# Main_Board.net
KiCad netlist of a schematic drawn in Altium Designer
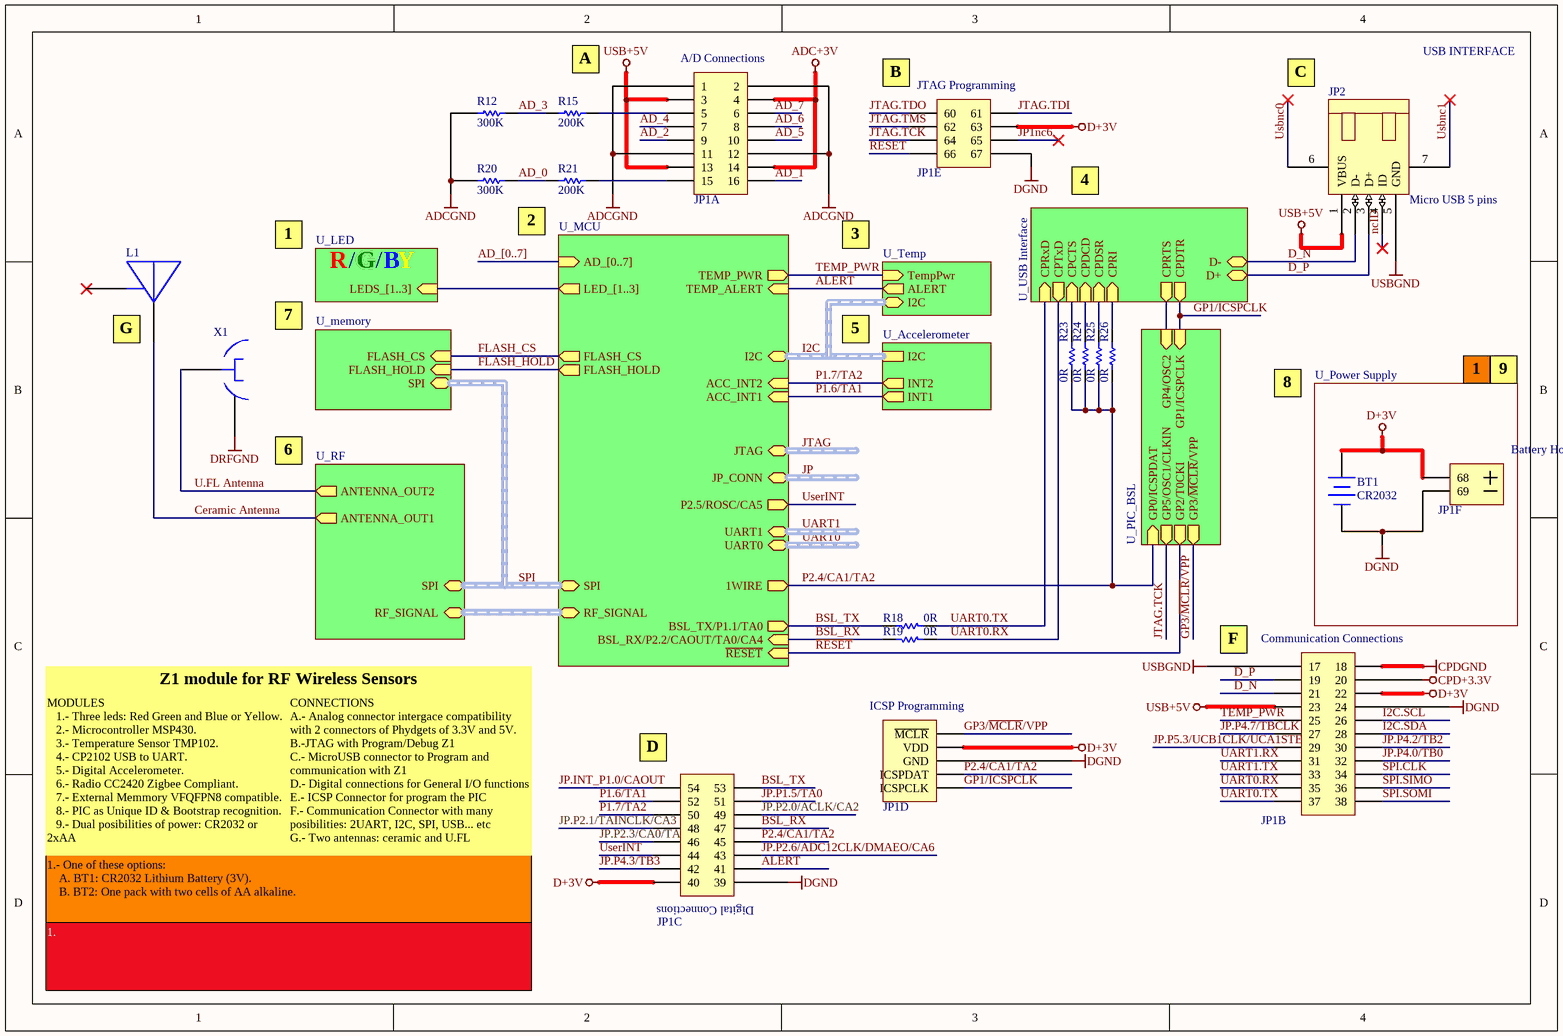
[diagram p0: Main Board.SchDoc]

(export (version "E")
  (design (tool "Eeschema 10.0.6"))
  (components
    (comp (ref "BT1")
      (value "CR2032")
      (footprint "CR2032 - 796136-1")
      (description "Multicell Battery")
      (libsource (lib "Z1_Project") (part "Battery"))
    )
    (comp (ref "JP1")
      (value "Z1 Expansion Connector")
      (footprint "Z1 Expansion Connectors_RC2")
      (libsource (lib "Z1_Project") (part "Z1_RC1"))
    )
    (comp (ref "JP2")
      (value "Micro USB 5 pins")
      (footprint "ZX62D-B-5P8")
      (libsource (lib "Z1_Project") (part "USB 5 pins"))
    )
    (comp (ref "L1")
      (value "Ceramic Antenna")
      (footprint "YAGEO - CAW431115300245")
      (description "ANT 2.4GHZ 802.11 BLUETOOTH SMD")
      (libsource (lib "Z1_Project") (part "5.3x2.2 TDMA Antenna_1"))
    )
    (comp (ref "R12")
      (value "300K")
      (footprint "CR1005-0402")
      (description "Semiconductor Resistor")
      (fields (field (name "MANUFACTURER") "Generic Components") (field (name "Comment") "Res Semi"))
      (libsource (lib "Z1_Project") (part "Res Semi"))
    )
    (comp (ref "R15")
      (value "200K")
      (footprint "CR1005-0402")
      (description "Semiconductor Resistor")
      (fields (field (name "MANUFACTURER") "Generic Components") (field (name "Comment") "Res Semi"))
      (libsource (lib "Z1_Project") (part "Res Semi"))
    )
    (comp (ref "R18")
      (value "0R")
      (footprint "CR-0402-AL")
      (description "RES ZERO OHM 1/10W 5% 0402 SMD")
      (fields (field (name "Comment") "Res Semi"))
      (libsource (lib "Z1_Project") (part "Res Semi"))
    )
    (comp (ref "R19")
      (value "0R")
      (footprint "CR-0402-AL")
      (description "RES ZERO OHM 1/10W 5% 0402 SMD")
      (fields (field (name "Comment") "Res Semi"))
      (libsource (lib "Z1_Project") (part "Res Semi"))
    )
    (comp (ref "R20")
      (value "300K")
      (footprint "CR1005-0402")
      (description "Semiconductor Resistor")
      (fields (field (name "MANUFACTURER") "Generic Components") (field (name "Comment") "Res Semi"))
      (libsource (lib "Z1_Project") (part "Res Semi"))
    )
    (comp (ref "R21")
      (value "200K")
      (footprint "CR1005-0402")
      (description "Semiconductor Resistor")
      (fields (field (name "MANUFACTURER") "Generic Components") (field (name "Comment") "Res Semi"))
      (libsource (lib "Z1_Project") (part "Res Semi"))
    )
    (comp (ref "R23")
      (value "0R")
      (footprint "CR-0402-AL")
      (description "Semiconductor Resistor")
      (fields (field (name "MANUFACTURER") "Generic Components") (field (name "Comment") "Res Semi"))
      (libsource (lib "Z1_Project") (part "Res Semi"))
    )
    (comp (ref "R24")
      (value "0R")
      (footprint "CR-0402-AL")
      (description "Semiconductor Resistor")
      (fields (field (name "MANUFACTURER") "Generic Components") (field (name "Comment") "Res Semi"))
      (libsource (lib "Z1_Project") (part "Res Semi"))
    )
    (comp (ref "R25")
      (value "0R")
      (footprint "CR-0402-AL")
      (description "Semiconductor Resistor")
      (fields (field (name "MANUFACTURER") "Generic Components") (field (name "Comment") "Res Semi"))
      (libsource (lib "Z1_Project") (part "Res Semi"))
    )
    (comp (ref "R26")
      (value "0R")
      (footprint "CR-0402-AL")
      (description "Semiconductor Resistor")
      (fields (field (name "MANUFACTURER") "Generic Components") (field (name "Comment") "Res Semi"))
      (libsource (lib "Z1_Project") (part "Res Semi"))
    )
    (comp (ref "X1")
      (value "U.FL RF Connector")
      (footprint "U.FL")
      (description "CONN RF MICROCOAXIAL SMD GOLD")
      (libsource (lib "Z1_Project") (part "AntennaOmnidirectional"))
    )
  )
  (nets
    (net (code "7") (name "/AD_0") (class "Default")
      (node (ref "R20") (pin "1") (pinfunction "1_1") (pintype "passive"))
      (node (ref "R21") (pin "2") (pinfunction "2_2") (pintype "passive"))
    )
    (net (code "8") (name "/AD_1") (class "Default")
      (node (ref "JP1") (pin "16") (pinfunction "16_16") (pintype "passive"))
    )
    (net (code "9") (name "/AD_2") (class "Default")
      (node (ref "JP1") (pin "9") (pinfunction "9_9") (pintype "passive"))
    )
    (net (code "10") (name "/AD_3") (class "Default")
      (node (ref "R12") (pin "1") (pinfunction "1_1") (pintype "passive"))
      (node (ref "R15") (pin "2") (pinfunction "2_2") (pintype "passive"))
    )
    (net (code "11") (name "/AD_4") (class "Default")
      (node (ref "JP1") (pin "7") (pinfunction "7_7") (pintype "passive"))
    )
    (net (code "12") (name "/AD_5") (class "Default")
      (node (ref "JP1") (pin "10") (pinfunction "10_10") (pintype "passive"))
    )
    (net (code "13") (name "/AD_6") (class "Default")
      (node (ref "JP1") (pin "8") (pinfunction "8_8") (pintype "passive"))
    )
    (net (code "14") (name "/AD_7") (class "Default")
      (node (ref "JP1") (pin "6") (pinfunction "6_6") (pintype "passive"))
    )
    (net (code "16") (name "/ALERT") (class "Default")
      (node (ref "JP1") (pin "41") (pinfunction "41_41") (pintype "passive"))
    )
    (net (code "17") (name "/BSL_RX") (class "Default")
      (node (ref "JP1") (pin "47") (pinfunction "47_47") (pintype "passive"))
      (node (ref "R19") (pin "2") (pinfunction "2_2") (pintype "passive"))
    )
    (net (code "18") (name "/BSL_TX") (class "Default")
      (node (ref "JP1") (pin "53") (pinfunction "53_53") (pintype "passive"))
      (node (ref "R18") (pin "2") (pinfunction "2_2") (pintype "passive"))
    )
    (net (code "19") (name "/CPCTS") (class "Default")
      (node (ref "R23") (pin "1") (pinfunction "1_1") (pintype "passive"))
    )
    (net (code "20") (name "/CPDCD") (class "Default")
      (node (ref "R24") (pin "1") (pinfunction "1_1") (pintype "passive"))
    )
    (net (code "21") (name "/CPDSR") (class "Default")
      (node (ref "R25") (pin "1") (pinfunction "1_1") (pintype "passive"))
    )
    (net (code "22") (name "/CPRI") (class "Default")
      (node (ref "R26") (pin "1") (pinfunction "1_1") (pintype "passive"))
    )
    (net (code "24") (name "/Ceramic Antenna") (class "Default")
      (node (ref "L1") (pin "1") (pinfunction "+_1") (pintype "passive"))
    )
    (net (code "25") (name "/D_N") (class "Default")
      (node (ref "JP1") (pin "21") (pinfunction "21_21") (pintype "passive"))
      (node (ref "JP2") (pin "2") (pinfunction "D-_2") (pintype "bidirectional"))
    )
    (net (code "26") (name "/D_P") (class "Default")
      (node (ref "JP1") (pin "19") (pinfunction "19_19") (pintype "passive"))
      (node (ref "JP2") (pin "3") (pinfunction "D+_3") (pintype "bidirectional"))
    )
    (net (code "29") (name "/GP1{slash}ICSPCLK") (class "Default")
      (node (ref "JP1") (pin "59") (pinfunction "59_59") (pintype "passive"))
    )
    (net (code "30") (name "/GP3{slash}~{MCLR}{slash}VPP") (class "Default")
      (node (ref "JP1") (pin "55") (pinfunction "55_55") (pintype "passive"))
    )
    (net (code "31") (name "/I2C.SCL") (class "Default")
      (node (ref "JP1") (pin "26") (pinfunction "26_26") (pintype "passive"))
    )
    (net (code "32") (name "/I2C.SDA") (class "Default")
      (node (ref "JP1") (pin "28") (pinfunction "28_28") (pintype "passive"))
    )
    (net (code "34") (name "/JP.INT_P1.0{slash}CAOUT") (class "Default")
      (node (ref "JP1") (pin "54") (pinfunction "54_54") (pintype "passive"))
    )
    (net (code "35") (name "/JP.P1.5{slash}TA0") (class "Default")
      (node (ref "JP1") (pin "51") (pinfunction "51_51") (pintype "passive"))
    )
    (net (code "36") (name "/JP.P2.0{slash}ACLK{slash}CA2") (class "Default")
      (node (ref "JP1") (pin "49") (pinfunction "49_49") (pintype "passive"))
    )
    (net (code "37") (name "/JP.P2.1{slash}TAINCLK{slash}CA3") (class "Default")
      (node (ref "JP1") (pin "48") (pinfunction "48_48") (pintype "passive"))
    )
    (net (code "38") (name "/JP.P2.3{slash}CA0{slash}TA1") (class "Default")
      (node (ref "JP1") (pin "46") (pinfunction "46_46") (pintype "passive"))
    )
    (net (code "39") (name "/JP.P2.6{slash}ADC12CLK{slash}DMAEO{slash}CA6") (class "Default")
      (node (ref "JP1") (pin "43") (pinfunction "43_43") (pintype "passive"))
    )
    (net (code "40") (name "/JP.P4.0{slash}TB0") (class "Default")
      (node (ref "JP1") (pin "32") (pinfunction "32_32") (pintype "passive"))
    )
    (net (code "41") (name "/JP.P4.2{slash}TB2") (class "Default")
      (node (ref "JP1") (pin "30") (pinfunction "30_30") (pintype "passive"))
    )
    (net (code "42") (name "/JP.P4.3{slash}TB3") (class "Default")
      (node (ref "JP1") (pin "42") (pinfunction "42_42") (pintype "passive"))
    )
    (net (code "43") (name "/JP.P4.7{slash}TBCLK") (class "Default")
      (node (ref "JP1") (pin "27") (pinfunction "27_27") (pintype "passive"))
    )
    (net (code "44") (name "/JP.P5.3{slash}UCB1CLK{slash}UCA1STE") (class "Default")
      (node (ref "JP1") (pin "29") (pinfunction "29_29") (pintype "passive"))
    )
    (net (code "45") (name "/JP1nc6") (class "Default")
      (node (ref "JP1") (pin "65") (pinfunction "65_65") (pintype "passive+no_connect"))
    )
    (net (code "46") (name "/JTAG.TCK") (class "Default")
      (node (ref "JP1") (pin "64") (pinfunction "64_64") (pintype "passive"))
    )
    (net (code "47") (name "/JTAG.TDI") (class "Default")
      (node (ref "JP1") (pin "61") (pinfunction "61_61") (pintype "passive"))
    )
    (net (code "48") (name "/JTAG.TDO") (class "Default")
      (node (ref "JP1") (pin "60") (pinfunction "60_60") (pintype "passive"))
    )
    (net (code "49") (name "/JTAG.TMS") (class "Default")
      (node (ref "JP1") (pin "62") (pinfunction "62_62") (pintype "passive"))
    )
    (net (code "51") (name "/P1.6{slash}TA1") (class "Default")
      (node (ref "JP1") (pin "52") (pinfunction "52_52") (pintype "passive"))
    )
    (net (code "52") (name "/P1.7{slash}TA2") (class "Default")
      (node (ref "JP1") (pin "50") (pinfunction "50_50") (pintype "passive"))
    )
    (net (code "53") (name "/P2.4{slash}CA1{slash}TA2") (class "Default")
      (node (ref "JP1") (pin "45") (pinfunction "45_45") (pintype "passive"))
      (node (ref "JP1") (pin "58") (pinfunction "58_58") (pintype "passive"))
      (node (ref "R23") (pin "2") (pinfunction "2_2") (pintype "passive"))
      (node (ref "R24") (pin "2") (pinfunction "2_2") (pintype "passive"))
      (node (ref "R25") (pin "2") (pinfunction "2_2") (pintype "passive"))
      (node (ref "R26") (pin "2") (pinfunction "2_2") (pintype "passive"))
    )
    (net (code "55") (name "/SPI.CLK") (class "Default")
      (node (ref "JP1") (pin "34") (pinfunction "34_34") (pintype "passive"))
    )
    (net (code "56") (name "/SPI.SIMO") (class "Default")
      (node (ref "JP1") (pin "36") (pinfunction "36_36") (pintype "passive"))
    )
    (net (code "57") (name "/SPI.SOMI") (class "Default")
      (node (ref "JP1") (pin "38") (pinfunction "38_38") (pintype "passive"))
    )
    (net (code "59") (name "/TEMP_PWR") (class "Default")
      (node (ref "JP1") (pin "25") (pinfunction "25_25") (pintype "passive"))
    )
    (net (code "60") (name "/U.FL Antenna") (class "Default")
      (node (ref "X1") (pin "1") (pinfunction "+_1") (pintype "passive"))
    )
    (net (code "61") (name "/UART0.RX") (class "Default")
      (node (ref "JP1") (pin "35") (pinfunction "35_35") (pintype "passive"))
      (node (ref "R19") (pin "1") (pinfunction "1_1") (pintype "passive"))
    )
    (net (code "62") (name "/UART0.TX") (class "Default")
      (node (ref "JP1") (pin "37") (pinfunction "37_37") (pintype "passive"))
      (node (ref "R18") (pin "1") (pinfunction "1_1") (pintype "passive"))
    )
    (net (code "63") (name "/UART1.RX") (class "Default")
      (node (ref "JP1") (pin "31") (pinfunction "31_31") (pintype "passive"))
    )
    (net (code "64") (name "/UART1.TX") (class "Default")
      (node (ref "JP1") (pin "33") (pinfunction "33_33") (pintype "passive"))
    )
    (net (code "65") (name "/Usbnc0") (class "Default")
      (node (ref "JP2") (pin "6") (pinfunction "SH2_6") (pintype "passive+no_connect"))
    )
    (net (code "66") (name "/Usbnc1") (class "Default")
      (node (ref "JP2") (pin "7") (pinfunction "SH1_7") (pintype "passive+no_connect"))
    )
    (net (code "67") (name "/UserINT") (class "Default")
      (node (ref "JP1") (pin "44") (pinfunction "44_44") (pintype "passive"))
    )
    (net (code "68") (name "/ncID") (class "Default")
      (node (ref "JP2") (pin "4") (pinfunction "ID_4") (pintype "bidirectional+no_connect"))
    )
    (net (code "75") (name "/~{RESET}") (class "Default")
      (node (ref "JP1") (pin "66") (pinfunction "66_66") (pintype "passive"))
    )
    (net (code "76") (name "ADC+3V") (class "Default")
      (node (ref "JP1") (pin "14") (pinfunction "14_14") (pintype "passive"))
      (node (ref "JP1") (pin "4") (pinfunction "4_4") (pintype "passive"))
    )
    (net (code "77") (name "ADCGND") (class "Default")
      (node (ref "JP1") (pin "1") (pinfunction "1_1") (pintype "passive"))
      (node (ref "JP1") (pin "11") (pinfunction "11_11") (pintype "passive"))
      (node (ref "JP1") (pin "12") (pinfunction "12_12") (pintype "passive"))
      (node (ref "JP1") (pin "2") (pinfunction "2_2") (pintype "passive"))
      (node (ref "R12") (pin "2") (pinfunction "2_2") (pintype "passive"))
      (node (ref "R20") (pin "2") (pinfunction "2_2") (pintype "passive"))
    )
    (net (code "78") (name "CPD+3.3V") (class "Default")
      (node (ref "JP1") (pin "20") (pinfunction "20_20") (pintype "passive"))
    )
    (net (code "79") (name "CPDGND") (class "Default")
      (node (ref "JP1") (pin "18") (pinfunction "18_18") (pintype "passive"))
    )
    (net (code "80") (name "D+3V") (class "Default")
      (node (ref "BT1") (pin "1") (pinfunction "+_1") (pintype "passive"))
      (node (ref "JP1") (pin "22") (pinfunction "22_22") (pintype "passive"))
      (node (ref "JP1") (pin "40") (pinfunction "40_40") (pintype "passive"))
      (node (ref "JP1") (pin "56") (pinfunction "56_56") (pintype "passive"))
      (node (ref "JP1") (pin "63") (pinfunction "63_63") (pintype "passive"))
      (node (ref "JP1") (pin "68") (pinfunction "68_68") (pintype "passive"))
    )
    (net (code "81") (name "DGND") (class "Default")
      (node (ref "BT1") (pin "2") (pinfunction "-_2") (pintype "passive"))
      (node (ref "JP1") (pin "24") (pinfunction "24_24") (pintype "passive"))
      (node (ref "JP1") (pin "39") (pinfunction "39_39") (pintype "passive"))
      (node (ref "JP1") (pin "57") (pinfunction "57_57") (pintype "passive"))
      (node (ref "JP1") (pin "67") (pinfunction "67_67") (pintype "passive"))
      (node (ref "JP1") (pin "69") (pinfunction "69_69") (pintype "passive"))
    )
    (net (code "82") (name "DRFGND") (class "Default")
      (node (ref "X1") (pin "2") (pinfunction "GND_2") (pintype "passive"))
    )
    (net (code "83") (name "Net-(JP1-Pad5)") (class "Default")
      (node (ref "JP1") (pin "5") (pinfunction "5_5") (pintype "passive"))
      (node (ref "R15") (pin "1") (pinfunction "1_1") (pintype "passive"))
    )
    (net (code "84") (name "Net-(JP1-Pad15)") (class "Default")
      (node (ref "JP1") (pin "15") (pinfunction "15_15") (pintype "passive"))
      (node (ref "R21") (pin "1") (pinfunction "1_1") (pintype "passive"))
    )
    (net (code "85") (name "USB+5V") (class "Default")
      (node (ref "JP1") (pin "13") (pinfunction "13_13") (pintype "passive"))
      (node (ref "JP1") (pin "23") (pinfunction "23_23") (pintype "passive"))
      (node (ref "JP1") (pin "3") (pinfunction "3_3") (pintype "passive"))
      (node (ref "JP2") (pin "1") (pinfunction "VBUS_1") (pintype "power_in"))
    )
    (net (code "86") (name "USBGND") (class "Default")
      (node (ref "JP1") (pin "17") (pinfunction "17_17") (pintype "passive"))
      (node (ref "JP2") (pin "5") (pinfunction "GND_5") (pintype "passive"))
    )
    (net (code "87") (name "unconnected-(L1-GND-Pad2)") (class "Default")
      (node (ref "L1") (pin "2") (pinfunction "GND_2") (pintype "passive+no_connect"))
    )
  )
)
